# 2_PIS____BHC-A-2030-01____V1_0_16.net
KiCad netlist of a schematic drawn in Altium Designer
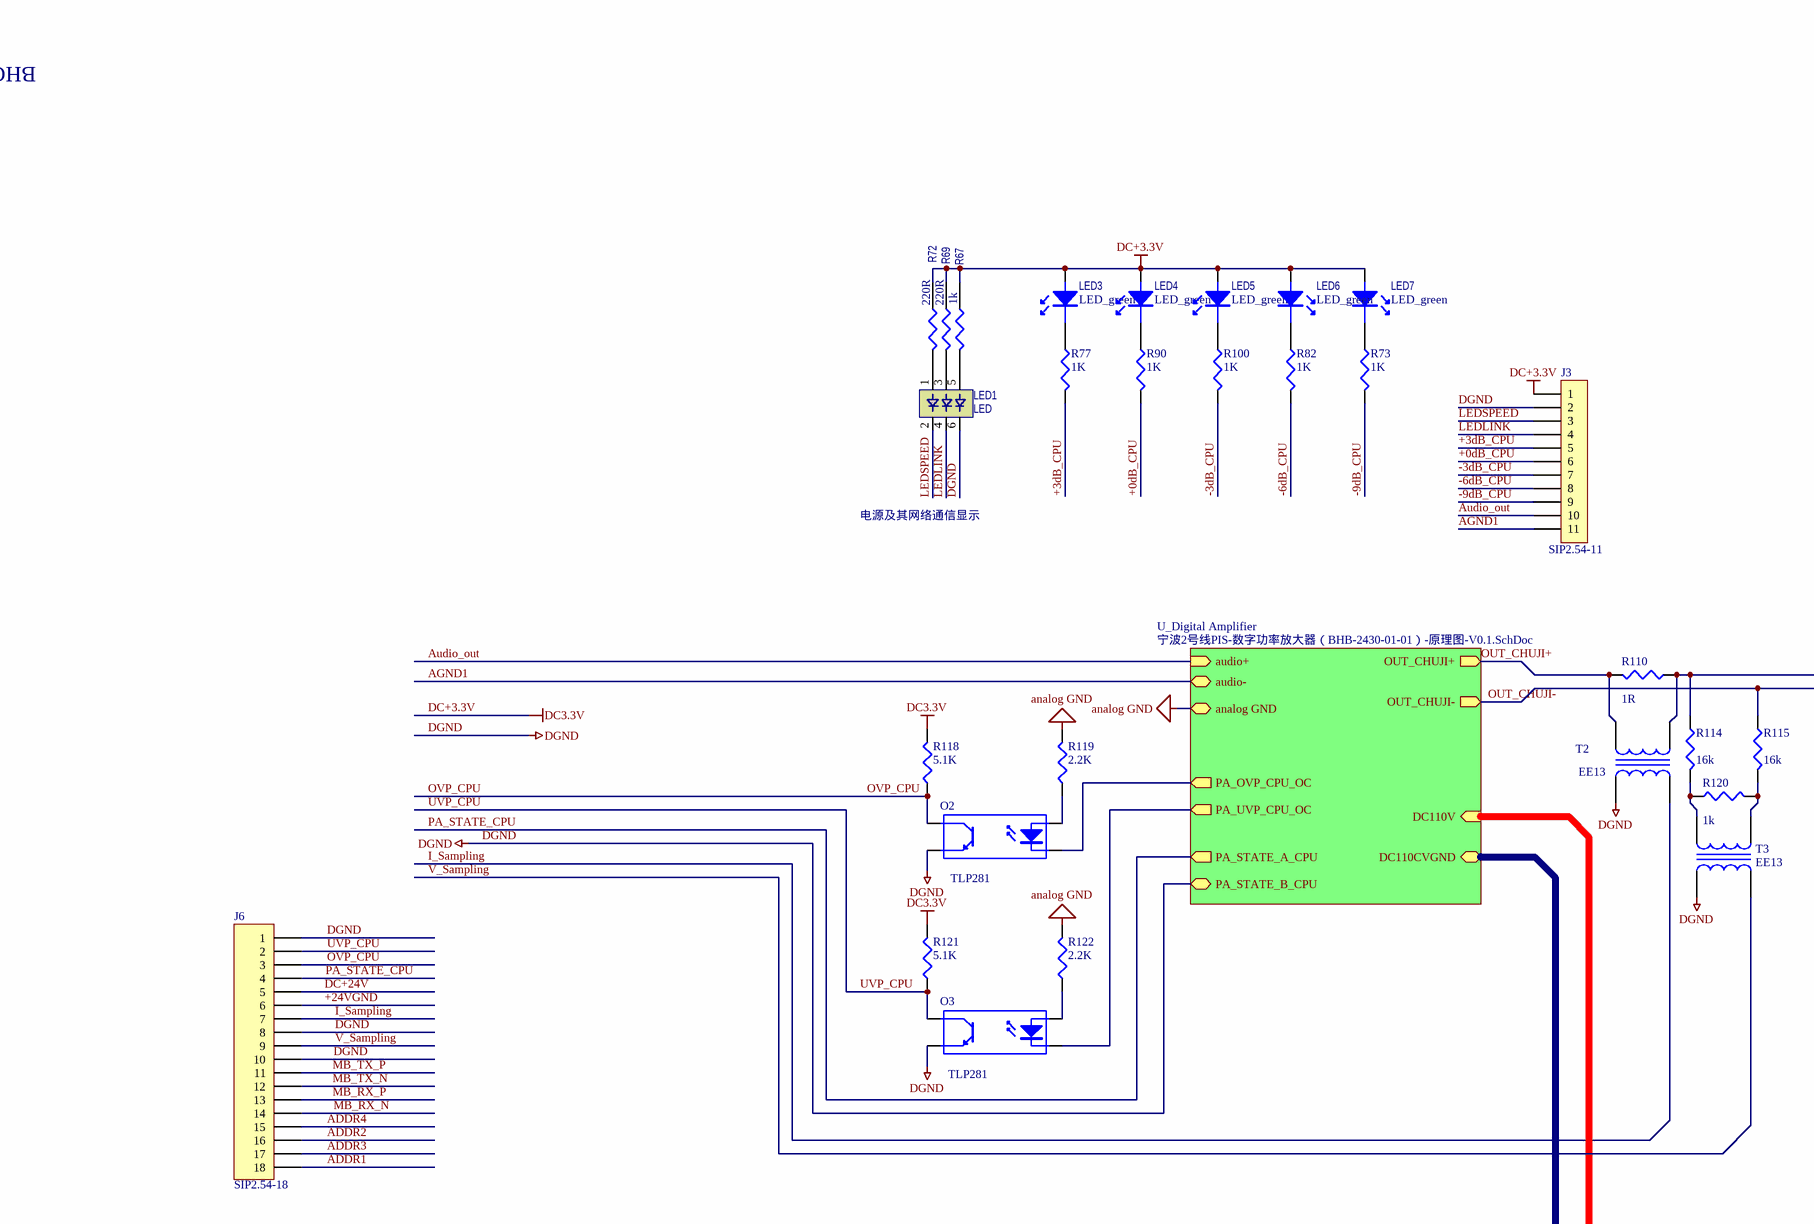
[diagram p0: 宁波2号线PIS_数字功率放大器_功放板(BHC-A-2030-01)_原理图_V1.0 (16).SchDoc, top left]
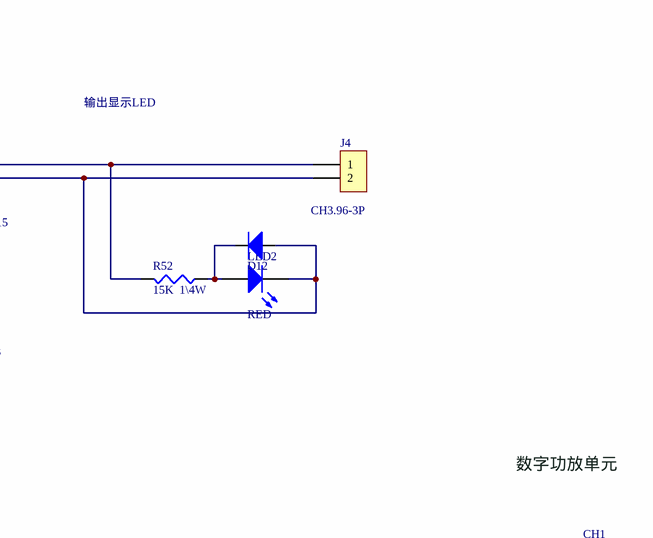
[diagram p1: 宁波2号线PIS_数字功率放大器_功放板(BHC-A-2030-01)_原理图_V1.0 (16).SchDoc, top right]
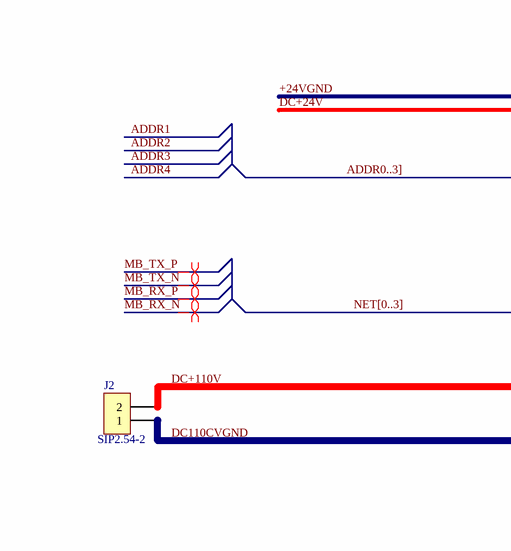
[diagram p2: 宁波2号线PIS_数字功率放大器_功放板(BHC-A-2030-01)_原理图_V1.0 (16).SchDoc, bottom left]
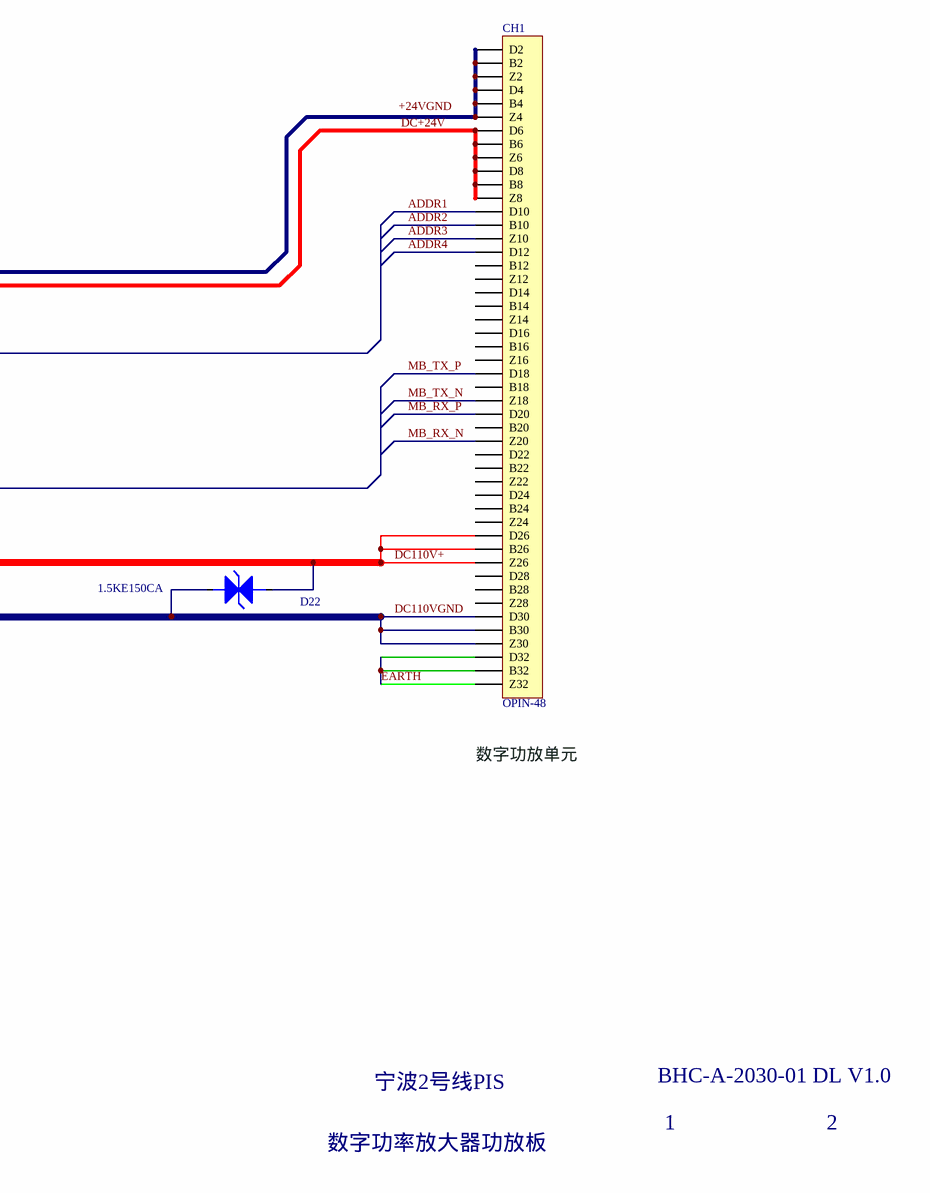
[diagram p3: 宁波2号线PIS_数字功率放大器_功放板(BHC-A-2030-01)_原理图_V1.0 (16).SchDoc, bottom right]

(export (version "E")
  (design (tool "Eeschema 10.0.6"))
  (components
    (comp (ref "CH1") (value "OPIN-48") (footprint "OPIN-48f") (libsource (lib "SCH") (part "OPIN-48")))
    (comp (ref "D12")
      (value "DIODE")
      (footprint "7227AK")
      (description "Default Diode")
      (libsource (lib "SCH") (part "DIODE"))
    )
    (comp (ref "D22")
      (value "1.5KE150CA")
      (footprint "TVS-CA")
      (fields (field (name "Comment") "D_TVS"))
      (libsource (lib "SCH") (part "D_TVS"))
    )
    (comp (ref "J2")
      (value "SIP2.54-2")
      (footprint "SIP2.54-2")
      (description "Connector")
      (fields (field (name "Comment") "CON2"))
      (libsource (lib "SCH") (part "CON2"))
    )
    (comp (ref "J3")
      (value "SIP2.54-11")
      (footprint "SIP2.54-11")
      (fields (field (name "Comment") "CON11"))
      (libsource (lib "SCH") (part "CON11"))
    )
    (comp (ref "J4")
      (value "CH3.96-3P")
      (footprint "CH3.96-3P+")
      (description "Connector")
      (fields (field (name "Comment") "CON2"))
      (libsource (lib "") (part "CON2_1"))
    )
    (comp (ref "J6")
      (value "SIP2.54-18")
      (footprint "SIP2.54-18")
      (description "Connector")
      (fields (field (name "Comment") "CON18"))
      (libsource (lib "SCH") (part "CON18"))
    )
    (comp (ref "LED1") (value "LED") (footprint "LED-3-3-L") (libsource (lib "*") (part "3-LED")))
    (comp (ref "LED2")
      (value "RED")
      (footprint "LED-3-L")
      (description "Typical RED, GREEN, YELLOW, AMBER GaAs LED")
      (fields (field (name "PUBLISHER") "Altium Limited"))
      (libsource (lib "Miscellaneous Devices") (part "LED2"))
    )
    (comp (ref "LED3") (value "LED_green") (footprint "LED-3-L") (libsource (lib "*") (part "LED")))
    (comp (ref "LED4") (value "LED_green") (footprint "LED-3-L") (libsource (lib "*") (part "LED")))
    (comp (ref "LED5") (value "LED_green") (footprint "LED-3-L") (libsource (lib "*") (part "LED")))
    (comp (ref "LED6") (value "LED_green") (footprint "LED-3-L") (libsource (lib "*") (part "LED")))
    (comp (ref "LED7") (value "LED_green") (footprint "LED-3-L") (libsource (lib "*") (part "LED")))
    (comp (ref "O2")
      (value "TLP281")
      (footprint "SOP4")
      (description "4-Pin Phototransistor Optocoupler")
      (fields (field (name "PUBLISHER") "Altium Limited"))
      (libsource (lib "Miscellaneous Devices") (part "Optoisolator1"))
    )
    (comp (ref "O3")
      (value "TLP281")
      (footprint "SOP4")
      (description "4-Pin Phototransistor Optocoupler")
      (fields (field (name "PUBLISHER") "Altium Limited"))
      (libsource (lib "Miscellaneous Devices") (part "Optoisolator1"))
    )
    (comp (ref "R52")
      (value "15K  ~{1}4W")
      (footprint "R-1/4W")
      (description "Resistor")
      (fields (field (name "PUBLISHER") "Altium Limited"))
      (libsource (lib "Miscellaneous Devices") (part "Res3"))
    )
    (comp (ref "R67") (value "1k") (footprint "M0805") (libsource (lib "*") (part "RES1")))
    (comp (ref "R69") (value "220R") (footprint "M0805") (libsource (lib "*") (part "RES1")))
    (comp (ref "R72") (value "220R") (footprint "M0805") (libsource (lib "*") (part "RES1")))
    (comp (ref "R73")
      (value "1K")
      (footprint "M0805")
      (description "Resistor")
      (fields (field (name "Comment") "11k") (field (name "PUBLISHER") "Altium Limited"))
      (libsource (lib "Miscellaneous Devices") (part "Res3"))
    )
    (comp (ref "R77")
      (value "1K")
      (footprint "M0805")
      (description "Resistor")
      (fields (field (name "Comment") "11k") (field (name "PUBLISHER") "Altium Limited"))
      (libsource (lib "Miscellaneous Devices") (part "Res3"))
    )
    (comp (ref "R82")
      (value "1K")
      (footprint "M0805")
      (description "Resistor")
      (fields (field (name "Comment") "11k") (field (name "PUBLISHER") "Altium Limited"))
      (libsource (lib "Miscellaneous Devices") (part "Res3"))
    )
    (comp (ref "R90")
      (value "1K")
      (footprint "M0805")
      (description "Resistor")
      (fields (field (name "Comment") "11k") (field (name "PUBLISHER") "Altium Limited"))
      (libsource (lib "Miscellaneous Devices") (part "Res3"))
    )
    (comp (ref "R100")
      (value "1K")
      (footprint "M0805")
      (description "Resistor")
      (fields (field (name "Comment") "11k") (field (name "PUBLISHER") "Altium Limited"))
      (libsource (lib "Miscellaneous Devices") (part "Res3"))
    )
    (comp (ref "R110")
      (value "1R")
      (footprint "R-2W")
      (description "Resistor")
      (fields (field (name "PUBLISHER") "Altium Limited"))
      (libsource (lib "Miscellaneous Devices") (part "Res3"))
    )
    (comp (ref "R114")
      (value "16k")
      (footprint "R-1/4W")
      (description "Resistor")
      (fields (field (name "PUBLISHER") "Altium Limited"))
      (libsource (lib "Miscellaneous Devices") (part "Res3"))
    )
    (comp (ref "R115")
      (value "16k")
      (footprint "R-1/4W")
      (description "Resistor")
      (fields (field (name "PUBLISHER") "Altium Limited"))
      (libsource (lib "Miscellaneous Devices") (part "Res3"))
    )
    (comp (ref "R118")
      (value "5.1K")
      (footprint "M0805")
      (description "Resistor")
      (fields (field (name "PUBLISHER") "Altium Limited"))
      (libsource (lib "*") (part "Res3"))
    )
    (comp (ref "R119")
      (value "2.2K")
      (footprint "M0805")
      (description "Resistor")
      (fields (field (name "PUBLISHER") "Altium Limited"))
      (libsource (lib "*") (part "Res3"))
    )
    (comp (ref "R120")
      (value "1k")
      (footprint "R-1/4W")
      (description "Resistor")
      (fields (field (name "PUBLISHER") "Altium Limited"))
      (libsource (lib "Miscellaneous Devices") (part "Res3"))
    )
    (comp (ref "R121")
      (value "5.1K")
      (footprint "M0805")
      (description "Resistor")
      (fields (field (name "PUBLISHER") "Altium Limited"))
      (libsource (lib "*") (part "Res3"))
    )
    (comp (ref "R122")
      (value "2.2K")
      (footprint "M0805")
      (description "Resistor")
      (fields (field (name "PUBLISHER") "Altium Limited"))
      (libsource (lib "*") (part "Res3"))
    )
    (comp (ref "T2") (value "EE13") (footprint "EE13-C") (libsource (lib "SCH") (part "EE13")))
    (comp (ref "T3") (value "EE13") (footprint "EE13-C") (libsource (lib "SCH") (part "EE13")))
  )
  (nets
    (net (code "6") (name "/+0dB_CPU") (class "Default")
      (node (ref "J3") (pin "6") (pinfunction "6_6") (pintype "passive"))
      (node (ref "R90") (pin "2") (pinfunction "2_2") (pintype "passive"))
    )
    (net (code "7") (name "/+3dB_CPU") (class "Default")
      (node (ref "J3") (pin "5") (pinfunction "5_5") (pintype "passive"))
      (node (ref "R77") (pin "2") (pinfunction "2_2") (pintype "passive"))
    )
    (net (code "8") (name "/+24VGND") (class "Default")
      (node (ref "CH1") (pin "B2") (pinfunction "B2_B2") (pintype "passive"))
      (node (ref "CH1") (pin "B4") (pinfunction "B4_B4") (pintype "passive"))
      (node (ref "CH1") (pin "D2") (pinfunction "D2_D2") (pintype "passive"))
      (node (ref "CH1") (pin "D4") (pinfunction "D4_D4") (pintype "passive"))
      (node (ref "CH1") (pin "Z2") (pinfunction "Z2_Z2") (pintype "passive"))
      (node (ref "CH1") (pin "Z4") (pinfunction "Z4_Z4") (pintype "passive"))
      (node (ref "J6") (pin "6") (pinfunction "6_6") (pintype "passive"))
    )
    (net (code "9") (name "/-3dB_CPU") (class "Default")
      (node (ref "J3") (pin "7") (pinfunction "7_7") (pintype "passive"))
      (node (ref "R100") (pin "2") (pinfunction "2_2") (pintype "passive"))
    )
    (net (code "10") (name "/-6dB_CPU") (class "Default")
      (node (ref "J3") (pin "8") (pinfunction "8_8") (pintype "passive"))
      (node (ref "R82") (pin "1") (pinfunction "1_1") (pintype "passive"))
    )
    (net (code "11") (name "/-9dB_CPU") (class "Default")
      (node (ref "J3") (pin "9") (pinfunction "9_9") (pintype "passive"))
      (node (ref "R73") (pin "1") (pinfunction "1_1") (pintype "passive"))
    )
    (net (code "13") (name "/ADDR1") (class "Default")
      (node (ref "CH1") (pin "D10") (pinfunction "D10_D10") (pintype "passive"))
      (node (ref "J6") (pin "18") (pinfunction "18_18") (pintype "passive"))
    )
    (net (code "14") (name "/ADDR2") (class "Default")
      (node (ref "CH1") (pin "B10") (pinfunction "B10_B10") (pintype "passive"))
      (node (ref "J6") (pin "16") (pinfunction "16_16") (pintype "passive"))
    )
    (net (code "15") (name "/ADDR3") (class "Default")
      (node (ref "CH1") (pin "Z10") (pinfunction "Z10_Z10") (pintype "passive"))
      (node (ref "J6") (pin "17") (pinfunction "17_17") (pintype "passive"))
    )
    (net (code "16") (name "/ADDR4") (class "Default")
      (node (ref "CH1") (pin "D12") (pinfunction "D12_D12") (pintype "passive"))
      (node (ref "J6") (pin "15") (pinfunction "15_15") (pintype "passive"))
    )
    (net (code "17") (name "/AGND1") (class "Default")
      (node (ref "J3") (pin "11") (pinfunction "11_11") (pintype "passive"))
    )
    (net (code "18") (name "/Audio_out") (class "Default")
      (node (ref "J3") (pin "10") (pinfunction "10_10") (pintype "passive"))
    )
    (net (code "19") (name "/DC+24V") (class "Default")
      (node (ref "CH1") (pin "B6") (pinfunction "B6_B6") (pintype "passive"))
      (node (ref "CH1") (pin "B8") (pinfunction "B8_B8") (pintype "passive"))
      (node (ref "CH1") (pin "D6") (pinfunction "D6_D6") (pintype "passive"))
      (node (ref "CH1") (pin "D8") (pinfunction "D8_D8") (pintype "passive"))
      (node (ref "CH1") (pin "Z6") (pinfunction "Z6_Z6") (pintype "passive"))
      (node (ref "CH1") (pin "Z8") (pinfunction "Z8_Z8") (pintype "passive"))
      (node (ref "J6") (pin "5") (pinfunction "5_5") (pintype "passive"))
    )
    (net (code "20") (name "/DC+110V") (class "Default")
      (node (ref "CH1") (pin "B26") (pinfunction "B26_B26") (pintype "passive"))
      (node (ref "CH1") (pin "D26") (pinfunction "D26_D26") (pintype "passive"))
      (node (ref "CH1") (pin "Z26") (pinfunction "Z26_Z26") (pintype "passive"))
      (node (ref "D22") (pin "1") (pinfunction "1_1") (pintype "passive"))
      (node (ref "J2") (pin "2") (pinfunction "2_2") (pintype "passive"))
    )
    (net (code "21") (name "/DC110CVGND") (class "Default")
      (node (ref "CH1") (pin "B30") (pinfunction "B30_B30") (pintype "passive"))
      (node (ref "CH1") (pin "D30") (pinfunction "D30_D30") (pintype "passive"))
      (node (ref "CH1") (pin "Z30") (pinfunction "Z30_Z30") (pintype "passive"))
      (node (ref "D22") (pin "2") (pinfunction "2_2") (pintype "passive"))
      (node (ref "J2") (pin "1") (pinfunction "1_1") (pintype "passive"))
    )
    (net (code "22") (name "/EARTH") (class "Default")
      (node (ref "CH1") (pin "B32") (pinfunction "B32_B32") (pintype "passive"))
      (node (ref "CH1") (pin "D32") (pinfunction "D32_D32") (pintype "passive"))
      (node (ref "CH1") (pin "Z32") (pinfunction "Z32_Z32") (pintype "passive"))
    )
    (net (code "23") (name "/I_Sampling") (class "Default")
      (node (ref "J6") (pin "7") (pinfunction "7_7") (pintype "passive"))
      (node (ref "T2") (pin "2") (pinfunction "2_2") (pintype "passive"))
    )
    (net (code "24") (name "/LEDLINK") (class "Default")
      (node (ref "J3") (pin "4") (pinfunction "4_4") (pintype "passive"))
      (node (ref "LED1") (pin "4") (pinfunction "4_4") (pintype "passive"))
    )
    (net (code "25") (name "/LEDSPEED") (class "Default")
      (node (ref "J3") (pin "3") (pinfunction "3_3") (pintype "passive"))
      (node (ref "LED1") (pin "2") (pinfunction "2_2") (pintype "passive"))
    )
    (net (code "26") (name "/MB_RX_N") (class "Default")
      (node (ref "CH1") (pin "Z20") (pinfunction "Z20_Z20") (pintype "passive"))
      (node (ref "J6") (pin "14") (pinfunction "14_14") (pintype "passive"))
    )
    (net (code "27") (name "/MB_RX_P") (class "Default")
      (node (ref "CH1") (pin "D20") (pinfunction "D20_D20") (pintype "passive"))
      (node (ref "J6") (pin "13") (pinfunction "13_13") (pintype "passive"))
    )
    (net (code "28") (name "/MB_TX_N") (class "Default")
      (node (ref "CH1") (pin "Z18") (pinfunction "Z18_Z18") (pintype "passive"))
      (node (ref "J6") (pin "12") (pinfunction "12_12") (pintype "passive"))
    )
    (net (code "29") (name "/MB_TX_P") (class "Default")
      (node (ref "CH1") (pin "D18") (pinfunction "D18_D18") (pintype "passive"))
      (node (ref "J6") (pin "11") (pinfunction "11_11") (pintype "passive"))
    )
    (net (code "31") (name "/OUT_CHUJI+") (class "Default")
      (node (ref "R110") (pin "2") (pinfunction "2_2") (pintype "passive"))
      (node (ref "T2") (pin "5") (pinfunction "5_5") (pintype "passive"))
    )
    (net (code "32") (name "/OUT_CHUJI-") (class "Default")
      (node (ref "D12") (pin "A") (pinfunction "A_A") (pintype "passive"))
      (node (ref "J4") (pin "2") (pinfunction "2_2") (pintype "passive"))
      (node (ref "LED2") (pin "2") (pinfunction "K_2") (pintype "passive"))
      (node (ref "R115") (pin "1") (pinfunction "1_1") (pintype "passive"))
    )
    (net (code "33") (name "/OVP_CPU") (class "Default")
      (node (ref "J6") (pin "3") (pinfunction "3_3") (pintype "passive"))
      (node (ref "O2") (pin "4") (pinfunction "C_4") (pintype "passive"))
      (node (ref "R118") (pin "2") (pinfunction "2_2") (pintype "passive"))
    )
    (net (code "34") (name "/PA_OVP_CPU_OC") (class "Default")
      (node (ref "O2") (pin "2") (pinfunction "K_2") (pintype "passive"))
    )
    (net (code "35") (name "/PA_STATE_CPU") (class "Default")
      (node (ref "J6") (pin "4") (pinfunction "4_4") (pintype "passive"))
    )
    (net (code "36") (name "/PA_UVP_CPU_OC") (class "Default")
      (node (ref "O3") (pin "2") (pinfunction "K_2") (pintype "passive"))
    )
    (net (code "37") (name "/UVP_CPU") (class "Default")
      (node (ref "J6") (pin "2") (pinfunction "2_2") (pintype "passive"))
      (node (ref "O3") (pin "4") (pinfunction "C_4") (pintype "passive"))
      (node (ref "R121") (pin "2") (pinfunction "2_2") (pintype "passive"))
    )
    (net (code "38") (name "/V_Sampling") (class "Default")
      (node (ref "J6") (pin "9") (pinfunction "9_9") (pintype "passive"))
      (node (ref "T3") (pin "2") (pinfunction "2_2") (pintype "passive"))
    )
    (net (code "40") (name "DC+3.3V") (class "Default")
      (node (ref "J3") (pin "1") (pinfunction "1_1") (pintype "passive"))
      (node (ref "LED3") (pin "1") (pinfunction "1_1") (pintype "passive"))
      (node (ref "LED4") (pin "1") (pinfunction "1_1") (pintype "passive"))
      (node (ref "LED5") (pin "1") (pinfunction "1_1") (pintype "passive"))
      (node (ref "LED6") (pin "1") (pinfunction "1_1") (pintype "passive"))
      (node (ref "LED7") (pin "1") (pinfunction "1_1") (pintype "passive"))
      (node (ref "R118") (pin "1") (pinfunction "1_1") (pintype "passive"))
      (node (ref "R121") (pin "1") (pinfunction "1_1") (pintype "passive"))
      (node (ref "R67") (pin "2") (pinfunction "2_2") (pintype "passive"))
      (node (ref "R69") (pin "2") (pinfunction "2_2") (pintype "passive"))
      (node (ref "R72") (pin "2") (pinfunction "2_2") (pintype "passive"))
    )
    (net (code "41") (name "DGND") (class "Default")
      (node (ref "J3") (pin "2") (pinfunction "2_2") (pintype "passive"))
      (node (ref "J6") (pin "1") (pinfunction "1_1") (pintype "passive"))
      (node (ref "J6") (pin "10") (pinfunction "10_10") (pintype "passive"))
      (node (ref "J6") (pin "8") (pinfunction "8_8") (pintype "passive"))
      (node (ref "LED1") (pin "6") (pinfunction "6_6") (pintype "passive"))
      (node (ref "O2") (pin "3") (pinfunction "E_3") (pintype "passive"))
      (node (ref "O3") (pin "3") (pinfunction "E_3") (pintype "passive"))
      (node (ref "T2") (pin "1") (pinfunction "1_1") (pintype "passive"))
      (node (ref "T3") (pin "1") (pinfunction "1_1") (pintype "passive"))
    )
    (net (code "42") (name "Net-(J4-Pad1)") (class "Default")
      (node (ref "J4") (pin "1") (pinfunction "1_1") (pintype "passive"))
      (node (ref "R110") (pin "1") (pinfunction "1_1") (pintype "passive"))
      (node (ref "R114") (pin "1") (pinfunction "1_1") (pintype "passive"))
      (node (ref "R52") (pin "2") (pinfunction "2_2") (pintype "passive"))
      (node (ref "T2") (pin "3") (pinfunction "3_3") (pintype "passive"))
    )
    (net (code "43") (name "Net-(LED1-Pad1)") (class "Default")
      (node (ref "LED1") (pin "1") (pinfunction "1_1") (pintype "passive"))
      (node (ref "R72") (pin "1") (pinfunction "1_1") (pintype "passive"))
    )
    (net (code "44") (name "Net-(LED1-Pad3)") (class "Default")
      (node (ref "LED1") (pin "3") (pinfunction "3_3") (pintype "passive"))
      (node (ref "R69") (pin "1") (pinfunction "1_1") (pintype "passive"))
    )
    (net (code "45") (name "Net-(LED1-Pad5)") (class "Default")
      (node (ref "LED1") (pin "5") (pinfunction "5_5") (pintype "passive"))
      (node (ref "R67") (pin "1") (pinfunction "1_1") (pintype "passive"))
    )
    (net (code "46") (name "Net-(LED2-A)") (class "Default")
      (node (ref "D12") (pin "K") (pinfunction "K_K") (pintype "passive"))
      (node (ref "LED2") (pin "1") (pinfunction "A_1") (pintype "passive"))
      (node (ref "R52") (pin "1") (pinfunction "1_1") (pintype "passive"))
    )
    (net (code "47") (name "Net-(LED3-Pad2)") (class "Default")
      (node (ref "LED3") (pin "2") (pinfunction "2_2") (pintype "passive"))
      (node (ref "R77") (pin "1") (pinfunction "1_1") (pintype "passive"))
    )
    (net (code "48") (name "Net-(LED4-Pad2)") (class "Default")
      (node (ref "LED4") (pin "2") (pinfunction "2_2") (pintype "passive"))
      (node (ref "R90") (pin "1") (pinfunction "1_1") (pintype "passive"))
    )
    (net (code "49") (name "Net-(LED5-Pad2)") (class "Default")
      (node (ref "LED5") (pin "2") (pinfunction "2_2") (pintype "passive"))
      (node (ref "R100") (pin "1") (pinfunction "1_1") (pintype "passive"))
    )
    (net (code "50") (name "Net-(LED6-Pad2)") (class "Default")
      (node (ref "LED6") (pin "2") (pinfunction "2_2") (pintype "passive"))
      (node (ref "R82") (pin "2") (pinfunction "2_2") (pintype "passive"))
    )
    (net (code "51") (name "Net-(LED7-Pad2)") (class "Default")
      (node (ref "LED7") (pin "2") (pinfunction "2_2") (pintype "passive"))
      (node (ref "R73") (pin "2") (pinfunction "2_2") (pintype "passive"))
    )
    (net (code "52") (name "Net-(O2-A)") (class "Default")
      (node (ref "O2") (pin "1") (pinfunction "A_1") (pintype "passive"))
      (node (ref "R119") (pin "2") (pinfunction "2_2") (pintype "passive"))
    )
    (net (code "53") (name "Net-(O3-A)") (class "Default")
      (node (ref "O3") (pin "1") (pinfunction "A_1") (pintype "passive"))
      (node (ref "R122") (pin "2") (pinfunction "2_2") (pintype "passive"))
    )
    (net (code "54") (name "Net-(R114-Pad2)") (class "Default")
      (node (ref "R114") (pin "2") (pinfunction "2_2") (pintype "passive"))
      (node (ref "R120") (pin "1") (pinfunction "1_1") (pintype "passive"))
      (node (ref "T3") (pin "5") (pinfunction "5_5") (pintype "passive"))
    )
    (net (code "55") (name "Net-(R115-Pad2)") (class "Default")
      (node (ref "R115") (pin "2") (pinfunction "2_2") (pintype "passive"))
      (node (ref "R120") (pin "2") (pinfunction "2_2") (pintype "passive"))
      (node (ref "T3") (pin "3") (pinfunction "3_3") (pintype "passive"))
    )
    (net (code "56") (name "analog GND") (class "Default")
      (node (ref "R119") (pin "1") (pinfunction "1_1") (pintype "passive"))
      (node (ref "R122") (pin "1") (pinfunction "1_1") (pintype "passive"))
    )
    (net (code "57") (name "unconnected-(CH1-PadB12)") (class "Default")
      (node (ref "CH1") (pin "B12") (pinfunction "B12_B12") (pintype "passive"))
    )
    (net (code "58") (name "unconnected-(CH1-PadB14)") (class "Default")
      (node (ref "CH1") (pin "B14") (pinfunction "B14_B14") (pintype "passive"))
    )
    (net (code "59") (name "unconnected-(CH1-PadB16)") (class "Default")
      (node (ref "CH1") (pin "B16") (pinfunction "B16_B16") (pintype "passive"))
    )
    (net (code "60") (name "unconnected-(CH1-PadB18)") (class "Default")
      (node (ref "CH1") (pin "B18") (pinfunction "B18_B18") (pintype "passive"))
    )
    (net (code "61") (name "unconnected-(CH1-PadB20)") (class "Default")
      (node (ref "CH1") (pin "B20") (pinfunction "B20_B20") (pintype "passive"))
    )
    (net (code "62") (name "unconnected-(CH1-PadB22)") (class "Default")
      (node (ref "CH1") (pin "B22") (pinfunction "B22_B22") (pintype "passive"))
    )
    (net (code "63") (name "unconnected-(CH1-PadB24)") (class "Default")
      (node (ref "CH1") (pin "B24") (pinfunction "B24_B24") (pintype "passive"))
    )
    (net (code "64") (name "unconnected-(CH1-PadB28)") (class "Default")
      (node (ref "CH1") (pin "B28") (pinfunction "B28_B28") (pintype "passive"))
    )
    (net (code "65") (name "unconnected-(CH1-PadD14)") (class "Default")
      (node (ref "CH1") (pin "D14") (pinfunction "D14_D14") (pintype "passive"))
    )
    (net (code "66") (name "unconnected-(CH1-PadD16)") (class "Default")
      (node (ref "CH1") (pin "D16") (pinfunction "D16_D16") (pintype "passive"))
    )
    (net (code "67") (name "unconnected-(CH1-PadD22)") (class "Default")
      (node (ref "CH1") (pin "D22") (pinfunction "D22_D22") (pintype "passive"))
    )
    (net (code "68") (name "unconnected-(CH1-PadD24)") (class "Default")
      (node (ref "CH1") (pin "D24") (pinfunction "D24_D24") (pintype "passive"))
    )
    (net (code "69") (name "unconnected-(CH1-PadD28)") (class "Default")
      (node (ref "CH1") (pin "D28") (pinfunction "D28_D28") (pintype "passive"))
    )
    (net (code "70") (name "unconnected-(CH1-PadZ12)") (class "Default")
      (node (ref "CH1") (pin "Z12") (pinfunction "Z12_Z12") (pintype "passive"))
    )
    (net (code "71") (name "unconnected-(CH1-PadZ14)") (class "Default")
      (node (ref "CH1") (pin "Z14") (pinfunction "Z14_Z14") (pintype "passive"))
    )
    (net (code "72") (name "unconnected-(CH1-PadZ16)") (class "Default")
      (node (ref "CH1") (pin "Z16") (pinfunction "Z16_Z16") (pintype "passive"))
    )
    (net (code "73") (name "unconnected-(CH1-PadZ22)") (class "Default")
      (node (ref "CH1") (pin "Z22") (pinfunction "Z22_Z22") (pintype "passive"))
    )
    (net (code "74") (name "unconnected-(CH1-PadZ24)") (class "Default")
      (node (ref "CH1") (pin "Z24") (pinfunction "Z24_Z24") (pintype "passive"))
    )
    (net (code "75") (name "unconnected-(CH1-PadZ28)") (class "Default")
      (node (ref "CH1") (pin "Z28") (pinfunction "Z28_Z28") (pintype "passive"))
    )
    (net (code "76") (name "unconnected-(T2-Pad4)") (class "Default")
      (node (ref "T2") (pin "4") (pinfunction "4_4") (pintype "passive"))
    )
    (net (code "77") (name "unconnected-(T3-Pad4)") (class "Default")
      (node (ref "T3") (pin "4") (pinfunction "4_4") (pintype "passive"))
    )
  )
)
